# TC377TP_2.net
KiCad netlist of a schematic drawn in Altium Designer
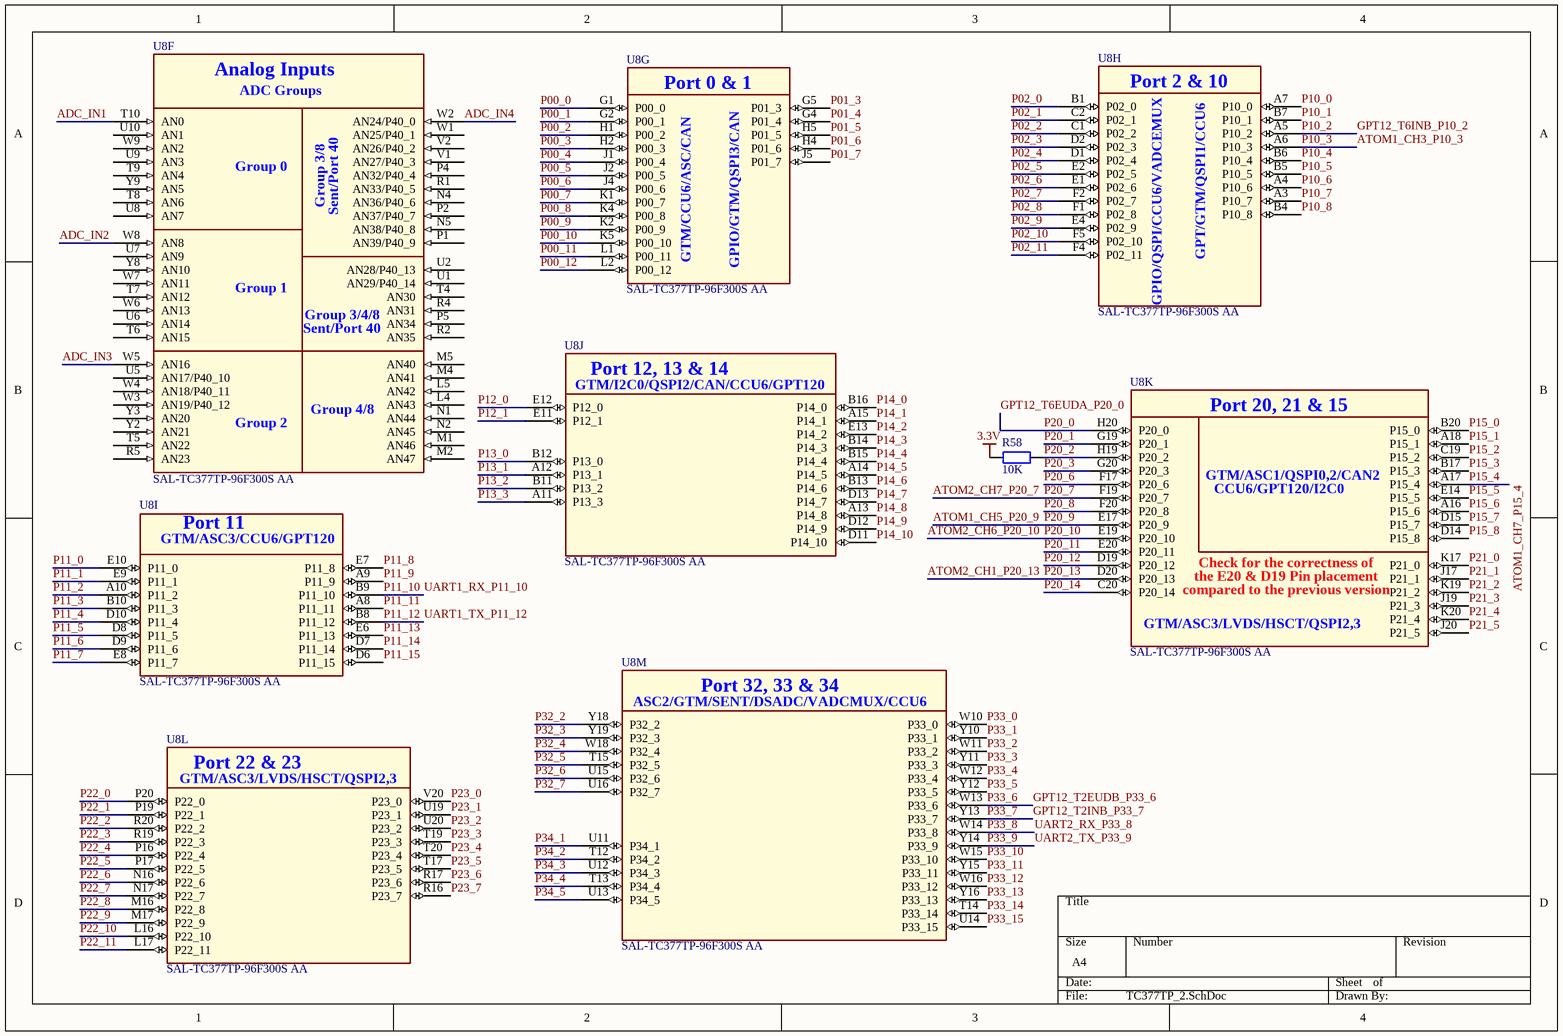
[diagram p0: TC377TP_2.SchDoc]

(export (version "E")
  (design (tool "Eeschema 10.0.6"))
  (components
    (comp (ref "R58")
      (value "10K")
      (footprint "R 0603_L")
      (description "贴片电阻")
      (fields (field (name "版权归属") "源创客"))
      (libsource (lib "3.1   - 电阻-电容-电感") (part "R"))
    )
    (comp (ref "U8")
      (value "SAL-TC377TP-96F300S AA")
      (footprint "BGA292C80P20X20")
      (description "32-Bit Single-Chip Microcontroller")
      (fields (field (name "MANUFACTURER") "Infineon Technologies"))
      (libsource (lib "SAL-TC377TP-96F300S AA") (part "SAL-TC377TP-96F300S AA"))
    )
  )
  (nets
    (net (code "1") (name "/ADC_IN1") (class "Default")
      (node (ref "U8") (pin "T10") (pinfunction "AN0_T10") (pintype "input"))
    )
    (net (code "2") (name "/ADC_IN2") (class "Default")
      (node (ref "U8") (pin "W8") (pinfunction "AN8_W8") (pintype "input"))
    )
    (net (code "3") (name "/ADC_IN3") (class "Default")
      (node (ref "U8") (pin "W5") (pinfunction "AN16_W5") (pintype "input"))
    )
    (net (code "4") (name "/ADC_IN4") (class "Default")
      (node (ref "U8") (pin "W2") (pinfunction "AN24/P40_0_W2") (pintype "input"))
    )
    (net (code "5") (name "/ATOM1_CH3_P10_3") (class "Default")
      (node (ref "U8") (pin "A6") (pinfunction "P10_3_A6") (pintype "bidirectional"))
    )
    (net (code "6") (name "/ATOM1_CH5_P20_9") (class "Default")
      (node (ref "U8") (pin "E17") (pinfunction "P20_9_E17") (pintype "bidirectional"))
    )
    (net (code "7") (name "/ATOM1_CH7_P15_4") (class "Default")
      (node (ref "U8") (pin "A17") (pinfunction "P15_4_A17") (pintype "bidirectional"))
    )
    (net (code "8") (name "/ATOM2_CH1_P20_13") (class "Default")
      (node (ref "U8") (pin "D20") (pinfunction "P20_13_D20") (pintype "bidirectional"))
    )
    (net (code "9") (name "/ATOM2_CH6_P20_10") (class "Default")
      (node (ref "U8") (pin "E19") (pinfunction "P20_10_E19") (pintype "bidirectional"))
    )
    (net (code "10") (name "/ATOM2_CH7_P20_7") (class "Default")
      (node (ref "U8") (pin "F19") (pinfunction "P20_7_F19") (pintype "bidirectional"))
    )
    (net (code "11") (name "/GPT12_T2EUDB_P33_6") (class "Default")
      (node (ref "U8") (pin "W13") (pinfunction "P33_6_W13") (pintype "bidirectional"))
    )
    (net (code "12") (name "/GPT12_T2INB_P33_7") (class "Default")
      (node (ref "U8") (pin "Y13") (pinfunction "P33_7_Y13") (pintype "bidirectional"))
    )
    (net (code "13") (name "/GPT12_T6EUDA_P20_0") (class "Default")
      (node (ref "U8") (pin "H20") (pinfunction "P20_0_H20") (pintype "bidirectional"))
    )
    (net (code "14") (name "/GPT12_T6INB_P10_2") (class "Default")
      (node (ref "U8") (pin "A5") (pinfunction "P10_2_A5") (pintype "bidirectional"))
    )
    (net (code "15") (name "/P00_0") (class "Default")
      (node (ref "U8") (pin "G1") (pinfunction "P00_0_G1") (pintype "bidirectional"))
    )
    (net (code "16") (name "/P00_1") (class "Default")
      (node (ref "U8") (pin "G2") (pinfunction "P00_1_G2") (pintype "bidirectional"))
    )
    (net (code "17") (name "/P00_2") (class "Default")
      (node (ref "U8") (pin "H1") (pinfunction "P00_2_H1") (pintype "bidirectional"))
    )
    (net (code "18") (name "/P00_3") (class "Default")
      (node (ref "U8") (pin "H2") (pinfunction "P00_3_H2") (pintype "bidirectional"))
    )
    (net (code "19") (name "/P00_4") (class "Default")
      (node (ref "U8") (pin "J1") (pinfunction "P00_4_J1") (pintype "bidirectional"))
    )
    (net (code "20") (name "/P00_5") (class "Default")
      (node (ref "U8") (pin "J2") (pinfunction "P00_5_J2") (pintype "bidirectional"))
    )
    (net (code "21") (name "/P00_6") (class "Default")
      (node (ref "U8") (pin "J4") (pinfunction "P00_6_J4") (pintype "bidirectional"))
    )
    (net (code "22") (name "/P00_7") (class "Default")
      (node (ref "U8") (pin "K1") (pinfunction "P00_7_K1") (pintype "bidirectional"))
    )
    (net (code "23") (name "/P00_8") (class "Default")
      (node (ref "U8") (pin "K4") (pinfunction "P00_8_K4") (pintype "bidirectional"))
    )
    (net (code "24") (name "/P00_9") (class "Default")
      (node (ref "U8") (pin "K2") (pinfunction "P00_9_K2") (pintype "bidirectional"))
    )
    (net (code "25") (name "/P00_10") (class "Default")
      (node (ref "U8") (pin "K5") (pinfunction "P00_10_K5") (pintype "bidirectional"))
    )
    (net (code "26") (name "/P00_11") (class "Default")
      (node (ref "U8") (pin "L1") (pinfunction "P00_11_L1") (pintype "bidirectional"))
    )
    (net (code "27") (name "/P00_12") (class "Default")
      (node (ref "U8") (pin "L2") (pinfunction "P00_12_L2") (pintype "bidirectional"))
    )
    (net (code "28") (name "/P01_3") (class "Default")
      (node (ref "U8") (pin "G5") (pinfunction "P01_3_G5") (pintype "bidirectional"))
    )
    (net (code "29") (name "/P01_4") (class "Default")
      (node (ref "U8") (pin "G4") (pinfunction "P01_4_G4") (pintype "bidirectional"))
    )
    (net (code "30") (name "/P01_5") (class "Default")
      (node (ref "U8") (pin "H5") (pinfunction "P01_5_H5") (pintype "bidirectional"))
    )
    (net (code "31") (name "/P01_6") (class "Default")
      (node (ref "U8") (pin "H4") (pinfunction "P01_6_H4") (pintype "bidirectional"))
    )
    (net (code "32") (name "/P01_7") (class "Default")
      (node (ref "U8") (pin "J5") (pinfunction "P01_7_J5") (pintype "bidirectional"))
    )
    (net (code "33") (name "/P02_0") (class "Default")
      (node (ref "U8") (pin "B1") (pinfunction "P02_0_B1") (pintype "bidirectional"))
    )
    (net (code "34") (name "/P02_1") (class "Default")
      (node (ref "U8") (pin "C2") (pinfunction "P02_1_C2") (pintype "bidirectional"))
    )
    (net (code "35") (name "/P02_2") (class "Default")
      (node (ref "U8") (pin "C1") (pinfunction "P02_2_C1") (pintype "bidirectional"))
    )
    (net (code "36") (name "/P02_3") (class "Default")
      (node (ref "U8") (pin "D2") (pinfunction "P02_3_D2") (pintype "bidirectional"))
    )
    (net (code "37") (name "/P02_4") (class "Default")
      (node (ref "U8") (pin "D1") (pinfunction "P02_4_D1") (pintype "bidirectional"))
    )
    (net (code "38") (name "/P02_5") (class "Default")
      (node (ref "U8") (pin "E2") (pinfunction "P02_5_E2") (pintype "bidirectional"))
    )
    (net (code "39") (name "/P02_6") (class "Default")
      (node (ref "U8") (pin "E1") (pinfunction "P02_6_E1") (pintype "bidirectional"))
    )
    (net (code "40") (name "/P02_7") (class "Default")
      (node (ref "U8") (pin "F2") (pinfunction "P02_7_F2") (pintype "bidirectional"))
    )
    (net (code "41") (name "/P02_8") (class "Default")
      (node (ref "U8") (pin "F1") (pinfunction "P02_8_F1") (pintype "bidirectional"))
    )
    (net (code "42") (name "/P02_9") (class "Default")
      (node (ref "U8") (pin "E4") (pinfunction "P02_9_E4") (pintype "bidirectional"))
    )
    (net (code "43") (name "/P02_10") (class "Default")
      (node (ref "U8") (pin "F5") (pinfunction "P02_10_F5") (pintype "bidirectional"))
    )
    (net (code "44") (name "/P02_11") (class "Default")
      (node (ref "U8") (pin "F4") (pinfunction "P02_11_F4") (pintype "bidirectional"))
    )
    (net (code "45") (name "/P10_0") (class "Default")
      (node (ref "U8") (pin "A7") (pinfunction "P10_0_A7") (pintype "bidirectional"))
    )
    (net (code "46") (name "/P10_1") (class "Default")
      (node (ref "U8") (pin "B7") (pinfunction "P10_1_B7") (pintype "bidirectional"))
    )
    (net (code "47") (name "/P10_4") (class "Default")
      (node (ref "U8") (pin "B6") (pinfunction "P10_4_B6") (pintype "bidirectional"))
    )
    (net (code "48") (name "/P10_5") (class "Default")
      (node (ref "U8") (pin "B5") (pinfunction "P10_5_B5") (pintype "bidirectional"))
    )
    (net (code "49") (name "/P10_6") (class "Default")
      (node (ref "U8") (pin "A4") (pinfunction "P10_6_A4") (pintype "bidirectional"))
    )
    (net (code "50") (name "/P10_7") (class "Default")
      (node (ref "U8") (pin "A3") (pinfunction "P10_7_A3") (pintype "bidirectional"))
    )
    (net (code "51") (name "/P10_8") (class "Default")
      (node (ref "U8") (pin "B4") (pinfunction "P10_8_B4") (pintype "bidirectional"))
    )
    (net (code "52") (name "/P11_0") (class "Default")
      (node (ref "U8") (pin "E10") (pinfunction "P11_0_E10") (pintype "bidirectional"))
    )
    (net (code "53") (name "/P11_1") (class "Default")
      (node (ref "U8") (pin "E9") (pinfunction "P11_1_E9") (pintype "bidirectional"))
    )
    (net (code "54") (name "/P11_2") (class "Default")
      (node (ref "U8") (pin "A10") (pinfunction "P11_2_A10") (pintype "bidirectional"))
    )
    (net (code "55") (name "/P11_3") (class "Default")
      (node (ref "U8") (pin "B10") (pinfunction "P11_3_B10") (pintype "bidirectional"))
    )
    (net (code "56") (name "/P11_4") (class "Default")
      (node (ref "U8") (pin "D10") (pinfunction "P11_4_D10") (pintype "bidirectional"))
    )
    (net (code "57") (name "/P11_5") (class "Default")
      (node (ref "U8") (pin "D8") (pinfunction "P11_5_D8") (pintype "bidirectional"))
    )
    (net (code "58") (name "/P11_6") (class "Default")
      (node (ref "U8") (pin "D9") (pinfunction "P11_6_D9") (pintype "bidirectional"))
    )
    (net (code "59") (name "/P11_7") (class "Default")
      (node (ref "U8") (pin "E8") (pinfunction "P11_7_E8") (pintype "bidirectional"))
    )
    (net (code "60") (name "/P11_8") (class "Default")
      (node (ref "U8") (pin "E7") (pinfunction "P11_8_E7") (pintype "bidirectional"))
    )
    (net (code "61") (name "/P11_9") (class "Default")
      (node (ref "U8") (pin "A9") (pinfunction "P11_9_A9") (pintype "bidirectional"))
    )
    (net (code "62") (name "/P11_10") (class "Default")
      (node (ref "U8") (pin "B9") (pinfunction "P11_10_B9") (pintype "bidirectional"))
    )
    (net (code "63") (name "/P11_11") (class "Default")
      (node (ref "U8") (pin "A8") (pinfunction "P11_11_A8") (pintype "bidirectional"))
    )
    (net (code "64") (name "/P11_12") (class "Default")
      (node (ref "U8") (pin "B8") (pinfunction "P11_12_B8") (pintype "bidirectional"))
    )
    (net (code "65") (name "/P11_13") (class "Default")
      (node (ref "U8") (pin "E6") (pinfunction "P11_13_E6") (pintype "bidirectional"))
    )
    (net (code "66") (name "/P11_14") (class "Default")
      (node (ref "U8") (pin "D7") (pinfunction "P11_14_D7") (pintype "bidirectional"))
    )
    (net (code "67") (name "/P11_15") (class "Default")
      (node (ref "U8") (pin "D6") (pinfunction "P11_15_D6") (pintype "bidirectional"))
    )
    (net (code "68") (name "/P12_0") (class "Default")
      (node (ref "U8") (pin "E12") (pinfunction "P12_0_E12") (pintype "bidirectional"))
    )
    (net (code "69") (name "/P12_1") (class "Default")
      (node (ref "U8") (pin "E11") (pinfunction "P12_1_E11") (pintype "bidirectional"))
    )
    (net (code "70") (name "/P13_0") (class "Default")
      (node (ref "U8") (pin "B12") (pinfunction "P13_0_B12") (pintype "bidirectional"))
    )
    (net (code "71") (name "/P13_1") (class "Default")
      (node (ref "U8") (pin "A12") (pinfunction "P13_1_A12") (pintype "bidirectional"))
    )
    (net (code "72") (name "/P13_2") (class "Default")
      (node (ref "U8") (pin "B11") (pinfunction "P13_2_B11") (pintype "bidirectional"))
    )
    (net (code "73") (name "/P13_3") (class "Default")
      (node (ref "U8") (pin "A11") (pinfunction "P13_3_A11") (pintype "bidirectional"))
    )
    (net (code "74") (name "/P14_0") (class "Default")
      (node (ref "U8") (pin "B16") (pinfunction "P14_0_B16") (pintype "bidirectional"))
    )
    (net (code "75") (name "/P14_1") (class "Default")
      (node (ref "U8") (pin "A15") (pinfunction "P14_1_A15") (pintype "bidirectional"))
    )
    (net (code "76") (name "/P14_2") (class "Default")
      (node (ref "U8") (pin "E13") (pinfunction "P14_2_E13") (pintype "bidirectional"))
    )
    (net (code "77") (name "/P14_3") (class "Default")
      (node (ref "U8") (pin "B14") (pinfunction "P14_3_B14") (pintype "bidirectional"))
    )
    (net (code "78") (name "/P14_4") (class "Default")
      (node (ref "U8") (pin "B15") (pinfunction "P14_4_B15") (pintype "bidirectional"))
    )
    (net (code "79") (name "/P14_5") (class "Default")
      (node (ref "U8") (pin "A14") (pinfunction "P14_5_A14") (pintype "bidirectional"))
    )
    (net (code "80") (name "/P14_6") (class "Default")
      (node (ref "U8") (pin "B13") (pinfunction "P14_6_B13") (pintype "bidirectional"))
    )
    (net (code "81") (name "/P14_7") (class "Default")
      (node (ref "U8") (pin "D13") (pinfunction "P14_7_D13") (pintype "bidirectional"))
    )
    (net (code "82") (name "/P14_8") (class "Default")
      (node (ref "U8") (pin "A13") (pinfunction "P14_8_A13") (pintype "bidirectional"))
    )
    (net (code "83") (name "/P14_9") (class "Default")
      (node (ref "U8") (pin "D12") (pinfunction "P14_9_D12") (pintype "bidirectional"))
    )
    (net (code "84") (name "/P14_10") (class "Default")
      (node (ref "U8") (pin "D11") (pinfunction "P14_10_D11") (pintype "bidirectional"))
    )
    (net (code "85") (name "/P15_0") (class "Default")
      (node (ref "U8") (pin "B20") (pinfunction "P15_0_B20") (pintype "bidirectional"))
    )
    (net (code "86") (name "/P15_1") (class "Default")
      (node (ref "U8") (pin "A18") (pinfunction "P15_1_A18") (pintype "bidirectional"))
    )
    (net (code "87") (name "/P15_2") (class "Default")
      (node (ref "U8") (pin "C19") (pinfunction "P15_2_C19") (pintype "bidirectional"))
    )
    (net (code "88") (name "/P15_3") (class "Default")
      (node (ref "U8") (pin "B17") (pinfunction "P15_3_B17") (pintype "bidirectional"))
    )
    (net (code "89") (name "/P15_5") (class "Default")
      (node (ref "U8") (pin "E14") (pinfunction "P15_5_E14") (pintype "bidirectional"))
    )
    (net (code "90") (name "/P15_6") (class "Default")
      (node (ref "U8") (pin "A16") (pinfunction "P15_6_A16") (pintype "bidirectional"))
    )
    (net (code "91") (name "/P15_7") (class "Default")
      (node (ref "U8") (pin "D15") (pinfunction "P15_7_D15") (pintype "bidirectional"))
    )
    (net (code "92") (name "/P15_8") (class "Default")
      (node (ref "U8") (pin "D14") (pinfunction "P15_8_D14") (pintype "bidirectional"))
    )
    (net (code "93") (name "/P20_1") (class "Default")
      (node (ref "U8") (pin "G19") (pinfunction "P20_1_G19") (pintype "bidirectional"))
    )
    (net (code "94") (name "/P20_2") (class "Default")
      (node (ref "R58") (pin "1") (pinfunction "1_1") (pintype "passive"))
      (node (ref "U8") (pin "H19") (pinfunction "P20_2_H19") (pintype "bidirectional"))
    )
    (net (code "95") (name "/P20_3") (class "Default")
      (node (ref "U8") (pin "G20") (pinfunction "P20_3_G20") (pintype "bidirectional"))
    )
    (net (code "96") (name "/P20_6") (class "Default")
      (node (ref "U8") (pin "F17") (pinfunction "P20_6_F17") (pintype "bidirectional"))
    )
    (net (code "97") (name "/P20_8") (class "Default")
      (node (ref "U8") (pin "F20") (pinfunction "P20_8_F20") (pintype "bidirectional"))
    )
    (net (code "98") (name "/P20_11") (class "Default")
      (node (ref "U8") (pin "E20") (pinfunction "P20_11_E20") (pintype "bidirectional"))
    )
    (net (code "99") (name "/P20_12") (class "Default")
      (node (ref "U8") (pin "D19") (pinfunction "P20_12_D19") (pintype "bidirectional"))
    )
    (net (code "100") (name "/P20_14") (class "Default")
      (node (ref "U8") (pin "C20") (pinfunction "P20_14_C20") (pintype "bidirectional"))
    )
    (net (code "101") (name "/P21_0") (class "Default")
      (node (ref "U8") (pin "K17") (pinfunction "P21_0_K17") (pintype "bidirectional"))
    )
    (net (code "102") (name "/P21_1") (class "Default")
      (node (ref "U8") (pin "J17") (pinfunction "P21_1_J17") (pintype "bidirectional"))
    )
    (net (code "103") (name "/P21_2") (class "Default")
      (node (ref "U8") (pin "K19") (pinfunction "P21_2_K19") (pintype "bidirectional"))
    )
    (net (code "104") (name "/P21_3") (class "Default")
      (node (ref "U8") (pin "J19") (pinfunction "P21_3_J19") (pintype "bidirectional"))
    )
    (net (code "105") (name "/P21_4") (class "Default")
      (node (ref "U8") (pin "K20") (pinfunction "P21_4_K20") (pintype "bidirectional"))
    )
    (net (code "106") (name "/P21_5") (class "Default")
      (node (ref "U8") (pin "J20") (pinfunction "P21_5_J20") (pintype "bidirectional"))
    )
    (net (code "107") (name "/P22_0") (class "Default")
      (node (ref "U8") (pin "P20") (pinfunction "P22_0_P20") (pintype "bidirectional"))
    )
    (net (code "108") (name "/P22_1") (class "Default")
      (node (ref "U8") (pin "P19") (pinfunction "P22_1_P19") (pintype "bidirectional"))
    )
    (net (code "109") (name "/P22_2") (class "Default")
      (node (ref "U8") (pin "R20") (pinfunction "P22_2_R20") (pintype "bidirectional"))
    )
    (net (code "110") (name "/P22_3") (class "Default")
      (node (ref "U8") (pin "R19") (pinfunction "P22_3_R19") (pintype "bidirectional"))
    )
    (net (code "111") (name "/P22_4") (class "Default")
      (node (ref "U8") (pin "P16") (pinfunction "P22_4_P16") (pintype "bidirectional"))
    )
    (net (code "112") (name "/P22_5") (class "Default")
      (node (ref "U8") (pin "P17") (pinfunction "P22_5_P17") (pintype "bidirectional"))
    )
    (net (code "113") (name "/P22_6") (class "Default")
      (node (ref "U8") (pin "N16") (pinfunction "P22_6_N16") (pintype "bidirectional"))
    )
    (net (code "114") (name "/P22_7") (class "Default")
      (node (ref "U8") (pin "N17") (pinfunction "P22_7_N17") (pintype "bidirectional"))
    )
    (net (code "115") (name "/P22_8") (class "Default")
      (node (ref "U8") (pin "M16") (pinfunction "P22_8_M16") (pintype "bidirectional"))
    )
    (net (code "116") (name "/P22_9") (class "Default")
      (node (ref "U8") (pin "M17") (pinfunction "P22_9_M17") (pintype "bidirectional"))
    )
    (net (code "117") (name "/P22_10") (class "Default")
      (node (ref "U8") (pin "L16") (pinfunction "P22_10_L16") (pintype "bidirectional"))
    )
    (net (code "118") (name "/P22_11") (class "Default")
      (node (ref "U8") (pin "L17") (pinfunction "P22_11_L17") (pintype "bidirectional"))
    )
    (net (code "119") (name "/P23_0") (class "Default")
      (node (ref "U8") (pin "V20") (pinfunction "P23_0_V20") (pintype "bidirectional"))
    )
    (net (code "120") (name "/P23_1") (class "Default")
      (node (ref "U8") (pin "U19") (pinfunction "P23_1_U19") (pintype "bidirectional"))
    )
    (net (code "121") (name "/P23_2") (class "Default")
      (node (ref "U8") (pin "U20") (pinfunction "P23_2_U20") (pintype "bidirectional"))
    )
    (net (code "122") (name "/P23_3") (class "Default")
      (node (ref "U8") (pin "T19") (pinfunction "P23_3_T19") (pintype "bidirectional"))
    )
    (net (code "123") (name "/P23_4") (class "Default")
      (node (ref "U8") (pin "T20") (pinfunction "P23_4_T20") (pintype "bidirectional"))
    )
    (net (code "124") (name "/P23_5") (class "Default")
      (node (ref "U8") (pin "T17") (pinfunction "P23_5_T17") (pintype "bidirectional"))
    )
    (net (code "125") (name "/P23_6") (class "Default")
      (node (ref "U8") (pin "R17") (pinfunction "P23_6_R17") (pintype "bidirectional"))
    )
    (net (code "126") (name "/P23_7") (class "Default")
      (node (ref "U8") (pin "R16") (pinfunction "P23_7_R16") (pintype "bidirectional"))
    )
    (net (code "127") (name "/P32_2") (class "Default")
      (node (ref "U8") (pin "Y18") (pinfunction "P32_2_Y18") (pintype "bidirectional"))
    )
    (net (code "128") (name "/P32_3") (class "Default")
      (node (ref "U8") (pin "Y19") (pinfunction "P32_3_Y19") (pintype "bidirectional"))
    )
    (net (code "129") (name "/P32_4") (class "Default")
      (node (ref "U8") (pin "W18") (pinfunction "P32_4_W18") (pintype "bidirectional"))
    )
    (net (code "130") (name "/P32_5") (class "Default")
      (node (ref "U8") (pin "T15") (pinfunction "P32_5_T15") (pintype "bidirectional"))
    )
    (net (code "131") (name "/P32_6") (class "Default")
      (node (ref "U8") (pin "U15") (pinfunction "P32_6_U15") (pintype "bidirectional"))
    )
    (net (code "132") (name "/P32_7") (class "Default")
      (node (ref "U8") (pin "U16") (pinfunction "P32_7_U16") (pintype "bidirectional"))
    )
    (net (code "133") (name "/P33_0") (class "Default")
      (node (ref "U8") (pin "W10") (pinfunction "P33_0_W10") (pintype "bidirectional"))
    )
    (net (code "134") (name "/P33_1") (class "Default")
      (node (ref "U8") (pin "Y10") (pinfunction "P33_1_Y10") (pintype "bidirectional"))
    )
    (net (code "135") (name "/P33_2") (class "Default")
      (node (ref "U8") (pin "W11") (pinfunction "P33_2_W11") (pintype "bidirectional"))
    )
    (net (code "136") (name "/P33_3") (class "Default")
      (node (ref "U8") (pin "Y11") (pinfunction "P33_3_Y11") (pintype "bidirectional"))
    )
    (net (code "137") (name "/P33_4") (class "Default")
      (node (ref "U8") (pin "W12") (pinfunction "P33_4_W12") (pintype "bidirectional"))
    )
    (net (code "138") (name "/P33_5") (class "Default")
      (node (ref "U8") (pin "Y12") (pinfunction "P33_5_Y12") (pintype "bidirectional"))
    )
    (net (code "139") (name "/P33_8") (class "Default")
      (node (ref "U8") (pin "W14") (pinfunction "P33_8_W14") (pintype "bidirectional"))
    )
    (net (code "140") (name "/P33_9") (class "Default")
      (node (ref "U8") (pin "Y14") (pinfunction "P33_9_Y14") (pintype "bidirectional"))
    )
    (net (code "141") (name "/P33_10") (class "Default")
      (node (ref "U8") (pin "W15") (pinfunction "P33_10_W15") (pintype "bidirectional"))
    )
    (net (code "142") (name "/P33_11") (class "Default")
      (node (ref "U8") (pin "Y15") (pinfunction "P33_11_Y15") (pintype "bidirectional"))
    )
    (net (code "143") (name "/P33_12") (class "Default")
      (node (ref "U8") (pin "W16") (pinfunction "P33_12_W16") (pintype "bidirectional"))
    )
    (net (code "144") (name "/P33_13") (class "Default")
      (node (ref "U8") (pin "Y16") (pinfunction "P33_13_Y16") (pintype "bidirectional"))
    )
    (net (code "145") (name "/P33_14") (class "Default")
      (node (ref "U8") (pin "T14") (pinfunction "P33_14_T14") (pintype "bidirectional"))
    )
    (net (code "146") (name "/P33_15") (class "Default")
      (node (ref "U8") (pin "U14") (pinfunction "P33_15_U14") (pintype "bidirectional"))
    )
    (net (code "147") (name "/P34_1") (class "Default")
      (node (ref "U8") (pin "U11") (pinfunction "P34_1_U11") (pintype "bidirectional"))
    )
    (net (code "148") (name "/P34_2") (class "Default")
      (node (ref "U8") (pin "T12") (pinfunction "P34_2_T12") (pintype "bidirectional"))
    )
    (net (code "149") (name "/P34_3") (class "Default")
      (node (ref "U8") (pin "U12") (pinfunction "P34_3_U12") (pintype "bidirectional"))
    )
    (net (code "150") (name "/P34_4") (class "Default")
      (node (ref "U8") (pin "T13") (pinfunction "P34_4_T13") (pintype "bidirectional"))
    )
    (net (code "151") (name "/P34_5") (class "Default")
      (node (ref "U8") (pin "U13") (pinfunction "P34_5_U13") (pintype "bidirectional"))
    )
    (net (code "152") (name "3.3V") (class "Default")
      (node (ref "R58") (pin "2") (pinfunction "2_2") (pintype "passive"))
    )
    (net (code "153") (name "unconnected-(U8F-AN1-PadU10)") (class "Default")
      (node (ref "U8") (pin "U10") (pinfunction "AN1_U10") (pintype "input"))
    )
    (net (code "154") (name "unconnected-(U8F-AN2-PadW9)") (class "Default")
      (node (ref "U8") (pin "W9") (pinfunction "AN2_W9") (pintype "input"))
    )
    (net (code "155") (name "unconnected-(U8F-AN3-PadU9)") (class "Default")
      (node (ref "U8") (pin "U9") (pinfunction "AN3_U9") (pintype "input"))
    )
    (net (code "156") (name "unconnected-(U8F-AN4-PadT9)") (class "Default")
      (node (ref "U8") (pin "T9") (pinfunction "AN4_T9") (pintype "input"))
    )
    (net (code "157") (name "unconnected-(U8F-AN5-PadY9)") (class "Default")
      (node (ref "U8") (pin "Y9") (pinfunction "AN5_Y9") (pintype "input"))
    )
    (net (code "158") (name "unconnected-(U8F-AN6-PadT8)") (class "Default")
      (node (ref "U8") (pin "T8") (pinfunction "AN6_T8") (pintype "input"))
    )
    (net (code "159") (name "unconnected-(U8F-AN7-PadU8)") (class "Default")
      (node (ref "U8") (pin "U8") (pinfunction "AN7_U8") (pintype "input"))
    )
    (net (code "160") (name "unconnected-(U8F-AN9-PadU7)") (class "Default")
      (node (ref "U8") (pin "U7") (pinfunction "AN9_U7") (pintype "input"))
    )
    (net (code "161") (name "unconnected-(U8F-AN10-PadY8)") (class "Default")
      (node (ref "U8") (pin "Y8") (pinfunction "AN10_Y8") (pintype "input"))
    )
    (net (code "162") (name "unconnected-(U8F-AN11-PadW7)") (class "Default")
      (node (ref "U8") (pin "W7") (pinfunction "AN11_W7") (pintype "input"))
    )
    (net (code "163") (name "unconnected-(U8F-AN12-PadT7)") (class "Default")
      (node (ref "U8") (pin "T7") (pinfunction "AN12_T7") (pintype "input"))
    )
    (net (code "164") (name "unconnected-(U8F-AN13-PadW6)") (class "Default")
      (node (ref "U8") (pin "W6") (pinfunction "AN13_W6") (pintype "input"))
    )
    (net (code "165") (name "unconnected-(U8F-AN14-PadU6)") (class "Default")
      (node (ref "U8") (pin "U6") (pinfunction "AN14_U6") (pintype "input"))
    )
    (net (code "166") (name "unconnected-(U8F-AN15-PadT6)") (class "Default")
      (node (ref "U8") (pin "T6") (pinfunction "AN15_T6") (pintype "input"))
    )
    (net (code "167") (name "unconnected-(U8F-AN17{slash}P40_10-PadU5)") (class "Default")
      (node (ref "U8") (pin "U5") (pinfunction "AN17/P40_10_U5") (pintype "input"))
    )
    (net (code "168") (name "unconnected-(U8F-AN18{slash}P40_11-PadW4)") (class "Default")
      (node (ref "U8") (pin "W4") (pinfunction "AN18/P40_11_W4") (pintype "input"))
    )
    (net (code "169") (name "unconnected-(U8F-AN19{slash}P40_12-PadW3)") (class "Default")
      (node (ref "U8") (pin "W3") (pinfunction "AN19/P40_12_W3") (pintype "input"))
    )
    (net (code "170") (name "unconnected-(U8F-AN20-PadY3)") (class "Default")
      (node (ref "U8") (pin "Y3") (pinfunction "AN20_Y3") (pintype "input"))
    )
    (net (code "171") (name "unconnected-(U8F-AN21-PadY2)") (class "Default")
      (node (ref "U8") (pin "Y2") (pinfunction "AN21_Y2") (pintype "input"))
    )
    (net (code "172") (name "unconnected-(U8F-AN22-PadT5)") (class "Default")
      (node (ref "U8") (pin "T5") (pinfunction "AN22_T5") (pintype "input"))
    )
    (net (code "173") (name "unconnected-(U8F-AN23-PadR5)") (class "Default")
      (node (ref "U8") (pin "R5") (pinfunction "AN23_R5") (pintype "input"))
    )
    (net (code "174") (name "unconnected-(U8F-AN25{slash}P40_1-PadW1)") (class "Default")
      (node (ref "U8") (pin "W1") (pinfunction "AN25/P40_1_W1") (pintype "input"))
    )
    (net (code "175") (name "unconnected-(U8F-AN26{slash}P40_2-PadV2)") (class "Default")
      (node (ref "U8") (pin "V2") (pinfunction "AN26/P40_2_V2") (pintype "input"))
    )
    (net (code "176") (name "unconnected-(U8F-AN27{slash}P40_3-PadV1)") (class "Default")
      (node (ref "U8") (pin "V1") (pinfunction "AN27/P40_3_V1") (pintype "input"))
    )
    (net (code "177") (name "unconnected-(U8F-AN28{slash}P40_13-PadU2)") (class "Default")
      (node (ref "U8") (pin "U2") (pinfunction "AN28/P40_13_U2") (pintype "input"))
    )
    (net (code "178") (name "unconnected-(U8F-AN29{slash}P40_14-PadU1)") (class "Default")
      (node (ref "U8") (pin "U1") (pinfunction "AN29/P40_14_U1") (pintype "input"))
    )
    (net (code "179") (name "unconnected-(U8F-AN30-PadT4)") (class "Default")
      (node (ref "U8") (pin "T4") (pinfunction "AN30_T4") (pintype "input"))
    )
    (net (code "180") (name "unconnected-(U8F-AN31-PadR4)") (class "Default")
      (node (ref "U8") (pin "R4") (pinfunction "AN31_R4") (pintype "input"))
    )
    (net (code "181") (name "unconnected-(U8F-AN32{slash}P40_4-PadP4)") (class "Default")
      (node (ref "U8") (pin "P4") (pinfunction "AN32/P40_4_P4") (pintype "input"))
    )
    (net (code "182") (name "unconnected-(U8F-AN33{slash}P40_5-PadR1)") (class "Default")
      (node (ref "U8") (pin "R1") (pinfunction "AN33/P40_5_R1") (pintype "input"))
    )
    (net (code "183") (name "unconnected-(U8F-AN34-PadP5)") (class "Default")
      (node (ref "U8") (pin "P5") (pinfunction "AN34_P5") (pintype "input"))
    )
    (net (code "184") (name "unconnected-(U8F-AN35-PadR2)") (class "Default")
      (node (ref "U8") (pin "R2") (pinfunction "AN35_R2") (pintype "input"))
    )
    (net (code "185") (name "unconnected-(U8F-AN36{slash}P40_6-PadN4)") (class "Default")
      (node (ref "U8") (pin "N4") (pinfunction "AN36/P40_6_N4") (pintype "input"))
    )
    (net (code "186") (name "unconnected-(U8F-AN37{slash}P40_7-PadP2)") (class "Default")
      (node (ref "U8") (pin "P2") (pinfunction "AN37/P40_7_P2") (pintype "input"))
    )
    (net (code "187") (name "unconnected-(U8F-AN38{slash}P40_8-PadN5)") (class "Default")
      (node (ref "U8") (pin "N5") (pinfunction "AN38/P40_8_N5") (pintype "input"))
    )
    (net (code "188") (name "unconnected-(U8F-AN39{slash}P40_9-PadP1)") (class "Default")
      (node (ref "U8") (pin "P1") (pinfunction "AN39/P40_9_P1") (pintype "input"))
    )
    (net (code "189") (name "unconnected-(U8F-AN40-PadM5)") (class "Default")
      (node (ref "U8") (pin "M5") (pinfunction "AN40_M5") (pintype "input"))
    )
    (net (code "190") (name "unconnected-(U8F-AN41-PadM4)") (class "Default")
      (node (ref "U8") (pin "M4") (pinfunction "AN41_M4") (pintype "input"))
    )
    (net (code "191") (name "unconnected-(U8F-AN42-PadL5)") (class "Default")
      (node (ref "U8") (pin "L5") (pinfunction "AN42_L5") (pintype "input"))
    )
    (net (code "192") (name "unconnected-(U8F-AN43-PadL4)") (class "Default")
      (node (ref "U8") (pin "L4") (pinfunction "AN43_L4") (pintype "input"))
    )
    (net (code "193") (name "unconnected-(U8F-AN44-PadN1)") (class "Default")
      (node (ref "U8") (pin "N1") (pinfunction "AN44_N1") (pintype "input"))
    )
    (net (code "194") (name "unconnected-(U8F-AN45-PadN2)") (class "Default")
      (node (ref "U8") (pin "N2") (pinfunction "AN45_N2") (pintype "input"))
    )
    (net (code "195") (name "unconnected-(U8F-AN46-PadM1)") (class "Default")
      (node (ref "U8") (pin "M1") (pinfunction "AN46_M1") (pintype "input"))
    )
    (net (code "196") (name "unconnected-(U8F-AN47-PadM2)") (class "Default")
      (node (ref "U8") (pin "M2") (pinfunction "AN47_M2") (pintype "input"))
    )
  )
)
